# 09_POWER.net
KiCad netlist of a schematic drawn in Altium Designer
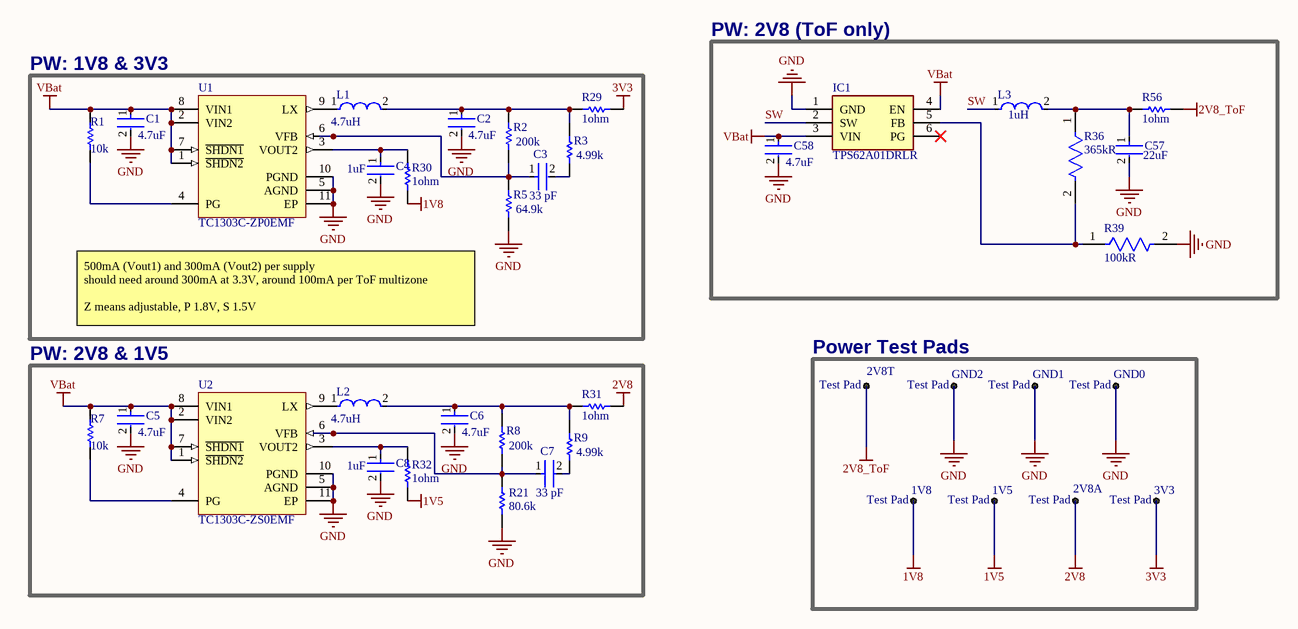
[diagram p0: 09_POWER.SchDoc]

(export (version "E")
  (design (tool "Eeschema 10.0.6"))
  (components
    (comp (ref "1V5")
      (value "Test Pad")
      (footprint "Pad-1.5mm")
      (description "1mm SMT Test Pad")
      (libsource (lib "gap9_deck") (part "CMP-01283-1"))
    )
    (comp (ref "1V8")
      (value "Test Pad")
      (footprint "Pad-1.5mm")
      (description "1mm SMT Test Pad")
      (libsource (lib "gap9_deck") (part "CMP-01283-1"))
    )
    (comp (ref "2V8A")
      (value "Test Pad")
      (footprint "Pad-1.5mm")
      (description "1mm SMT Test Pad")
      (libsource (lib "gap9_deck") (part "CMP-01283-1"))
    )
    (comp (ref "2V8T")
      (value "Test Pad")
      (footprint "Pad-1.5mm")
      (description "1mm SMT Test Pad")
      (libsource (lib "gap9_deck") (part "CMP-01283-1"))
    )
    (comp (ref "3V3")
      (value "Test Pad")
      (footprint "Pad-1.5mm")
      (description "1mm SMT Test Pad")
      (libsource (lib "gap9_deck") (part "CMP-01283-1"))
    )
    (comp (ref "C1")
      (value "4.7uF")
      (footprint "FP-C1005-050-0_15-MFG")
      (description "CAP CER 4.7UF 6.3V X5R 0402")
      (fields (field (name "VOLTAGE") "6.3V") (field (name "TOLERANCE") "10%"))
      (libsource (lib "Altium Content Vault") (part "02cd4be3c70576c341d710602a673aa"))
    )
    (comp (ref "C2")
      (value "4.7uF")
      (footprint "FP-C1005-050-0_15-MFG")
      (description "CAP CER 4.7UF 6.3V X5R 0402")
      (fields (field (name "VOLTAGE") "6.3V") (field (name "TOLERANCE") "10%"))
      (libsource (lib "Altium Content Vault") (part "02cd4be3c70576c341d710602a673aa"))
    )
    (comp (ref "C3")
      (value "33 pF")
      (footprint "FP-C0402-BB-MFG")
      (description "C0402 33 pF C0G 5.00% 50 V")
      (fields
        (field (name "OCTOPART") "https://octopart.com/c0402c330j5gac-kemet-2551464")
        (field (name "MANUFACTURER PART NUMBER") "C0402C330J5GAC")
      )
      (libsource (lib "Altium Content Vault") (part "b4654b650e69147ec39a6b967a45e02"))
    )
    (comp (ref "C4")
      (value "1uF")
      (footprint "FP-GRM155-0_05-IPC_B")
      (description "Chip Multilayer Ceramic Capacitors for General Purpose, 0402, 1.0uF, X5R, 15%, 20%, 25V")
      (fields (field (name "TOLERANCE") "20%") (field (name "Comment") "GRM155R61E105MA12D"))
      (libsource (lib "Altium Content Vault") (part "02cd4be3c70576c341d710602a673aa"))
    )
    (comp (ref "C5")
      (value "4.7uF")
      (footprint "FP-C1005-050-0_15-MFG")
      (description "CAP CER 4.7UF 6.3V X5R 0402")
      (fields (field (name "VOLTAGE") "6.3V") (field (name "TOLERANCE") "10%"))
      (libsource (lib "Altium Content Vault") (part "02cd4be3c70576c341d710602a673aa"))
    )
    (comp (ref "C6")
      (value "4.7uF")
      (footprint "FP-C1005-050-0_15-MFG")
      (description "CAP CER 4.7UF 6.3V X5R 0402")
      (fields (field (name "VOLTAGE") "6.3V") (field (name "TOLERANCE") "10%"))
      (libsource (lib "Altium Content Vault") (part "02cd4be3c70576c341d710602a673aa"))
    )
    (comp (ref "C7")
      (value "33 pF")
      (footprint "FP-C0402-BB-MFG")
      (description "C0402 33 pF C0G 5.00% 50 V")
      (fields
        (field (name "OCTOPART") "https://octopart.com/c0402c330j5gac-kemet-2551464")
        (field (name "MANUFACTURER PART NUMBER") "C0402C330J5GAC")
      )
      (libsource (lib "Altium Content Vault") (part "b4654b650e69147ec39a6b967a45e02"))
    )
    (comp (ref "C8")
      (value "1uF")
      (footprint "FP-GRM155-0_05-IPC_B")
      (description "Chip Multilayer Ceramic Capacitors for General Purpose, 0402, 1.0uF, X5R, 15%, 20%, 25V")
      (fields (field (name "TOLERANCE") "20%") (field (name "Comment") "GRM155R61E105MA12D"))
      (libsource (lib "Altium Content Vault") (part "02cd4be3c70576c341d710602a673aa"))
    )
    (comp (ref "C57")
      (value "22uF")
      (footprint "FP-GRM158-0_2-IPC_A")
      (description "CAP CER 22UF 6.3V X5R 0402")
      (fields (field (name "Comment") "GRM158R60J226ME01D"))
      (libsource (lib "Altium Content Vault") (part "b4654b650e69147ec39a6b967a45e02"))
    )
    (comp (ref "C58")
      (value "4.7uF")
      (footprint "FP-C1005-050-0_15-MFG")
      (description "CAP CER 4.7UF 6.3V X5R 0402")
      (fields (field (name "VOLTAGE") "6.3V") (field (name "TOLERANCE") "10%"))
      (libsource (lib "Altium Content Vault") (part "02cd4be3c70576c341d710602a673aa"))
    )
    (comp (ref "GND0")
      (value "Test Pad")
      (footprint "Pad-1.5mm")
      (description "1mm SMT Test Pad")
      (libsource (lib "gap9_deck") (part "CMP-01283-1"))
    )
    (comp (ref "GND1")
      (value "Test Pad")
      (footprint "Pad-1.5mm")
      (description "1mm SMT Test Pad")
      (libsource (lib "gap9_deck") (part "CMP-01283-1"))
    )
    (comp (ref "GND2")
      (value "Test Pad")
      (footprint "Pad-1.5mm")
      (description "1mm SMT Test Pad")
      (libsource (lib "gap9_deck") (part "CMP-01283-1"))
    )
    (comp (ref "IC1")
      (value "TPS62A01DRLR")
      (footprint "SamacSys:SOTFL50P160X60-6N")
      (description "Integrated Circuit")
      (fields (field (name "MOUSER PART NUMBER") "595-TPS62A01DRLR"))
      (libsource (lib "*") (part "TPS62A01DRLR"))
    )
    (comp (ref "L1")
      (value "LQM18FN4R7M00D")
      (footprint "FP-LQM18FN_00-IPC_A")
      (description "FIXED IND 4.7UH 80MA 600 MOHM")
      (fields (field (name "INDUCTANCE") "4.7uH") (field (name "TOLERANCE") "20%"))
      (libsource (lib "Altium Content Vault") (part "725321dda6339637d4d059423bc1c3c"))
    )
    (comp (ref "L2")
      (value "LQM18FN4R7M00D")
      (footprint "FP-LQM18FN_00-IPC_A")
      (description "FIXED IND 4.7UH 80MA 600 MOHM")
      (fields (field (name "INDUCTANCE") "4.7uH") (field (name "TOLERANCE") "20%"))
      (libsource (lib "Altium Content Vault") (part "725321dda6339637d4d059423bc1c3c"))
    )
    (comp (ref "L3")
      (value "1uH")
      (footprint "FP-CBL2012-MFG")
      (description "FIXED IND 1UH 950MA 195 MOHM SMD")
      (fields (field (name "TOLERANCE") "20%") (field (name "Comment") "CBL2012T1R0M"))
      (libsource (lib "Altium Content Vault") (part "725321dda6339637d4d059423bc1c3c"))
    )
    (comp (ref "R1")
      (value "10k")
      (footprint "RESC0603X28X15LL05T05")
      (fields (field (name "MANUFACTURER") "Vishay Dale") (field (name "PART NUMBER") "CRCW020110K0FNED"))
      (libsource (lib "Altium Content Vault") (part "RES"))
    )
    (comp (ref "R2")
      (value "200k")
      (footprint "RESC0603X28X15NL05T05")
      (fields (field (name "PART NUMBER") "CRCW0201200KFKED") (field (name "MANUFACTURER") "Vishay Dale"))
      (libsource (lib "Altium Content Vault") (part "RES"))
    )
    (comp (ref "R3")
      (value "4.99k")
      (footprint "RESC0603X28X15ML05T05")
      (fields (field (name "PART NUMBER") "CRCW02014K99FKED") (field (name "MANUFACTURER") "Vishay Dale"))
      (libsource (lib "Altium Content Vault") (part "RES"))
    )
    (comp (ref "R5")
      (value "64.9k")
      (footprint "RESC0603X28X15LL05T05")
      (fields (field (name "PART NUMBER") "CRCW020164K9FKED") (field (name "MANUFACTURER") "Vishay Dale"))
      (libsource (lib "Altium Content Vault") (part "RES"))
    )
    (comp (ref "R7")
      (value "10k")
      (footprint "RESC0603X28X15LL05T05")
      (fields (field (name "MANUFACTURER") "Vishay Dale") (field (name "PART NUMBER") "CRCW020110K0FNED"))
      (libsource (lib "Altium Content Vault") (part "RES"))
    )
    (comp (ref "R8")
      (value "200k")
      (footprint "RESC0603X28X15NL05T05")
      (fields (field (name "PART NUMBER") "CRCW0201200KFKED") (field (name "MANUFACTURER") "Vishay Dale"))
      (libsource (lib "Altium Content Vault") (part "RES"))
    )
    (comp (ref "R9")
      (value "4.99k")
      (footprint "RESC0603X28X15ML05T05")
      (fields (field (name "PART NUMBER") "CRCW02014K99FKED") (field (name "MANUFACTURER") "Vishay Dale"))
      (libsource (lib "Altium Content Vault") (part "RES"))
    )
    (comp (ref "R21")
      (value "80.6k")
      (footprint "RESC0603X28X15NL05T05")
      (fields (field (name "PART NUMBER") "CRCW020180K6FNED") (field (name "MANUFACTURER") "Vishay Dale"))
      (libsource (lib "Altium Content Vault") (part "RES"))
    )
    (comp (ref "R29")
      (value "1ohm")
      (footprint "RESC1005X40X25ML05T10")
      (fields (field (name "MANUFACTURER") "Vishay Dale") (field (name "PART NUMBER") "CRCW04021R00FKEDHP"))
      (libsource (lib "Altium Content Vault") (part "RES"))
    )
    (comp (ref "R30")
      (value "1ohm")
      (footprint "RESC1005X40X25ML05T10")
      (fields (field (name "MANUFACTURER") "Vishay Dale") (field (name "PART NUMBER") "CRCW04021R00FKEDHP"))
      (libsource (lib "Altium Content Vault") (part "RES"))
    )
    (comp (ref "R31")
      (value "1ohm")
      (footprint "RESC1005X40X25ML05T10")
      (fields (field (name "MANUFACTURER") "Vishay Dale") (field (name "PART NUMBER") "CRCW04021R00FKEDHP"))
      (libsource (lib "Altium Content Vault") (part "RES"))
    )
    (comp (ref "R32")
      (value "1ohm")
      (footprint "RESC1005X40X25ML05T10")
      (fields (field (name "MANUFACTURER") "Vishay Dale") (field (name "PART NUMBER") "CRCW04021R00FKEDHP"))
      (libsource (lib "Altium Content Vault") (part "RES"))
    )
    (comp (ref "R36")
      (value "365kR")
      (footprint "FP-CR0402-IPC_A")
      (description "Thick Film Chip Resistors 0402 365kΩ 0.0625W 1% 100ppm/°C")
      (fields (field (name "TOLERANCE") "1%") (field (name "Comment") "CR0402-FX-3653GLF"))
      (libsource (lib "Altium Content Vault") (part "1029c3af85768c4190bb7ad29bc67b5"))
    )
    (comp (ref "R39")
      (value "100kR")
      (footprint "FP-ERJ2RK-IPC_C")
      (description "RES SMD 100K OHM 1% 1/10W 0402")
      (fields (field (name "TOLERANCE") "1%") (field (name "Comment") "ERJ-2RKF1003X"))
      (libsource (lib "Altium Content Vault") (part "1029c3af85768c4190bb7ad29bc67b5"))
    )
    (comp (ref "R56")
      (value "1ohm")
      (footprint "RESC1005X40X25ML05T10")
      (fields (field (name "MANUFACTURER") "Vishay Dale") (field (name "PART NUMBER") "CRCW04021R00FKEDHP"))
      (libsource (lib "Altium Content Vault") (part "RES"))
    )
    (comp (ref "U1")
      (value "TC1303C-ZP0EMF")
      (footprint "DFN-MF10")
      (libsource (lib "Altium Content Vault") (part "PM-SWREG-TC1303ADJ-IL11"))
    )
    (comp (ref "U2")
      (value "TC1303C-ZS0EMF")
      (footprint "DFN-MF10")
      (libsource (lib "Altium Content Vault") (part "PM-SWREG-TC1303ADJ-IL11"))
    )
  )
  (nets
    (net (code "1") (name "/SW") (class "Default")
      (node (ref "IC1") (pin "2") (pinfunction "SW_2") (pintype "passive"))
      (node (ref "L3") (pin "1") (pinfunction "1_1") (pintype "passive"))
    )
    (net (code "2") (name "1V5") (class "Default")
      (node (ref "1V5") (pin "1") (pinfunction "1_1") (pintype "passive"))
      (node (ref "R32") (pin "2") (pinfunction "2_2") (pintype "passive"))
    )
    (net (code "3") (name "1V8") (class "Default")
      (node (ref "1V8") (pin "1") (pinfunction "1_1") (pintype "passive"))
      (node (ref "R30") (pin "2") (pinfunction "2_2") (pintype "passive"))
    )
    (net (code "4") (name "2V8") (class "Default")
      (node (ref "2V8A") (pin "1") (pinfunction "1_1") (pintype "passive"))
      (node (ref "R31") (pin "1") (pinfunction "1_1") (pintype "passive"))
    )
    (net (code "5") (name "2V8_ToF") (class "Default")
      (node (ref "2V8T") (pin "1") (pinfunction "1_1") (pintype "passive"))
      (node (ref "R56") (pin "1") (pinfunction "1_1") (pintype "passive"))
    )
    (net (code "6") (name "3V3") (class "Default")
      (node (ref "3V3") (pin "1") (pinfunction "1_1") (pintype "passive"))
      (node (ref "R29") (pin "1") (pinfunction "1_1") (pintype "passive"))
    )
    (net (code "7") (name "GND") (class "Default")
      (node (ref "C1") (pin "2") (pinfunction "2_2") (pintype "passive"))
      (node (ref "C2") (pin "2") (pinfunction "2_2") (pintype "passive"))
      (node (ref "C4") (pin "2") (pinfunction "2_2") (pintype "passive"))
      (node (ref "C5") (pin "2") (pinfunction "2_2") (pintype "passive"))
      (node (ref "C57") (pin "2") (pinfunction "2_2") (pintype "passive"))
      (node (ref "C58") (pin "2") (pinfunction "2_2") (pintype "passive"))
      (node (ref "C6") (pin "2") (pinfunction "2_2") (pintype "passive"))
      (node (ref "C8") (pin "2") (pinfunction "2_2") (pintype "passive"))
      (node (ref "GND0") (pin "1") (pinfunction "1_1") (pintype "passive"))
      (node (ref "GND1") (pin "1") (pinfunction "1_1") (pintype "passive"))
      (node (ref "GND2") (pin "1") (pinfunction "1_1") (pintype "passive"))
      (node (ref "IC1") (pin "1") (pinfunction "GND_1") (pintype "passive"))
      (node (ref "R21") (pin "1") (pinfunction "1_1") (pintype "passive"))
      (node (ref "R39") (pin "2") (pinfunction "2_2") (pintype "passive"))
      (node (ref "R5") (pin "1") (pinfunction "1_1") (pintype "passive"))
      (node (ref "U1") (pin "10") (pinfunction "PGND_10") (pintype "power_in"))
      (node (ref "U1") (pin "11") (pinfunction "EP_11") (pintype "power_in"))
      (node (ref "U1") (pin "5") (pinfunction "AGND_5") (pintype "power_in"))
      (node (ref "U2") (pin "10") (pinfunction "PGND_10") (pintype "power_in"))
      (node (ref "U2") (pin "11") (pinfunction "EP_11") (pintype "power_in"))
      (node (ref "U2") (pin "5") (pinfunction "AGND_5") (pintype "power_in"))
    )
    (net (code "8") (name "Net-(C2-Pad1)") (class "Default")
      (node (ref "C2") (pin "1") (pinfunction "1_1") (pintype "passive"))
      (node (ref "L1") (pin "2") (pinfunction "2_2") (pintype "passive"))
      (node (ref "R2") (pin "2") (pinfunction "2_2") (pintype "passive"))
      (node (ref "R29") (pin "2") (pinfunction "2_2") (pintype "passive"))
      (node (ref "R3") (pin "2") (pinfunction "2_2") (pintype "passive"))
    )
    (net (code "9") (name "Net-(C3-Pad2)") (class "Default")
      (node (ref "C3") (pin "2") (pinfunction "2_2") (pintype "passive"))
      (node (ref "R3") (pin "1") (pinfunction "1_1") (pintype "passive"))
    )
    (net (code "10") (name "Net-(C6-Pad1)") (class "Default")
      (node (ref "C6") (pin "1") (pinfunction "1_1") (pintype "passive"))
      (node (ref "L2") (pin "2") (pinfunction "2_2") (pintype "passive"))
      (node (ref "R31") (pin "2") (pinfunction "2_2") (pintype "passive"))
      (node (ref "R8") (pin "2") (pinfunction "2_2") (pintype "passive"))
      (node (ref "R9") (pin "2") (pinfunction "2_2") (pintype "passive"))
    )
    (net (code "11") (name "Net-(C7-Pad2)") (class "Default")
      (node (ref "C7") (pin "2") (pinfunction "2_2") (pintype "passive"))
      (node (ref "R9") (pin "1") (pinfunction "1_1") (pintype "passive"))
    )
    (net (code "12") (name "Net-(C57-Pad1)") (class "Default")
      (node (ref "C57") (pin "1") (pinfunction "1_1") (pintype "passive"))
      (node (ref "L3") (pin "2") (pinfunction "2_2") (pintype "passive"))
      (node (ref "R36") (pin "1") (pinfunction "1_1") (pintype "passive"))
      (node (ref "R56") (pin "2") (pinfunction "2_2") (pintype "passive"))
    )
    (net (code "13") (name "Net-(IC1-FB)") (class "Default")
      (node (ref "IC1") (pin "5") (pinfunction "FB_5") (pintype "passive"))
      (node (ref "R36") (pin "2") (pinfunction "2_2") (pintype "passive"))
      (node (ref "R39") (pin "1") (pinfunction "1_1") (pintype "passive"))
    )
    (net (code "14") (name "Net-(U1-LX)") (class "Default")
      (node (ref "L1") (pin "1") (pinfunction "1_1") (pintype "passive"))
      (node (ref "U1") (pin "9") (pinfunction "LX_9") (pintype "output"))
    )
    (net (code "15") (name "Net-(U1-PG)") (class "Default")
      (node (ref "R1") (pin "1") (pinfunction "1_1") (pintype "passive"))
      (node (ref "U1") (pin "4") (pinfunction "PG_4") (pintype "open_collector"))
    )
    (net (code "16") (name "Net-(U1-VFB)") (class "Default")
      (node (ref "C3") (pin "1") (pinfunction "1_1") (pintype "passive"))
      (node (ref "R2") (pin "1") (pinfunction "1_1") (pintype "passive"))
      (node (ref "R5") (pin "2") (pinfunction "2_2") (pintype "passive"))
      (node (ref "U1") (pin "6") (pinfunction "VFB_6") (pintype "input"))
    )
    (net (code "17") (name "Net-(U1-VOUT2)") (class "Default")
      (node (ref "C4") (pin "1") (pinfunction "1_1") (pintype "passive"))
      (node (ref "R30") (pin "1") (pinfunction "1_1") (pintype "passive"))
      (node (ref "U1") (pin "3") (pinfunction "VOUT2_3") (pintype "output"))
    )
    (net (code "18") (name "Net-(U2-LX)") (class "Default")
      (node (ref "L2") (pin "1") (pinfunction "1_1") (pintype "passive"))
      (node (ref "U2") (pin "9") (pinfunction "LX_9") (pintype "output"))
    )
    (net (code "19") (name "Net-(U2-PG)") (class "Default")
      (node (ref "R7") (pin "1") (pinfunction "1_1") (pintype "passive"))
      (node (ref "U2") (pin "4") (pinfunction "PG_4") (pintype "open_collector"))
    )
    (net (code "20") (name "Net-(U2-VFB)") (class "Default")
      (node (ref "C7") (pin "1") (pinfunction "1_1") (pintype "passive"))
      (node (ref "R21") (pin "2") (pinfunction "2_2") (pintype "passive"))
      (node (ref "R8") (pin "1") (pinfunction "1_1") (pintype "passive"))
      (node (ref "U2") (pin "6") (pinfunction "VFB_6") (pintype "input"))
    )
    (net (code "21") (name "Net-(U2-VOUT2)") (class "Default")
      (node (ref "C8") (pin "1") (pinfunction "1_1") (pintype "passive"))
      (node (ref "R32") (pin "1") (pinfunction "1_1") (pintype "passive"))
      (node (ref "U2") (pin "3") (pinfunction "VOUT2_3") (pintype "output"))
    )
    (net (code "22") (name "VBat") (class "Default")
      (node (ref "C1") (pin "1") (pinfunction "1_1") (pintype "passive"))
      (node (ref "C5") (pin "1") (pinfunction "1_1") (pintype "passive"))
      (node (ref "C58") (pin "1") (pinfunction "1_1") (pintype "passive"))
      (node (ref "IC1") (pin "3") (pinfunction "VIN_3") (pintype "passive"))
      (node (ref "IC1") (pin "4") (pinfunction "EN_4") (pintype "passive"))
      (node (ref "R1") (pin "2") (pinfunction "2_2") (pintype "passive"))
      (node (ref "R7") (pin "2") (pinfunction "2_2") (pintype "passive"))
      (node (ref "U1") (pin "1") (pinfunction "~{SHDN2}_1") (pintype "input"))
      (node (ref "U1") (pin "2") (pinfunction "VIN2_2") (pintype "power_in"))
      (node (ref "U1") (pin "7") (pinfunction "~{SHDN1}_7") (pintype "input"))
      (node (ref "U1") (pin "8") (pinfunction "VIN1_8") (pintype "power_in"))
      (node (ref "U2") (pin "1") (pinfunction "~{SHDN2}_1") (pintype "input"))
      (node (ref "U2") (pin "2") (pinfunction "VIN2_2") (pintype "power_in"))
      (node (ref "U2") (pin "7") (pinfunction "~{SHDN1}_7") (pintype "input"))
      (node (ref "U2") (pin "8") (pinfunction "VIN1_8") (pintype "power_in"))
    )
    (net (code "23") (name "unconnected-(IC1-PG-Pad6)") (class "Default")
      (node (ref "IC1") (pin "6") (pinfunction "PG_6") (pintype "passive+no_connect"))
    )
  )
)
